# US29080671_sheet1.net
KiCad netlist of a schematic drawn in Altium Designer
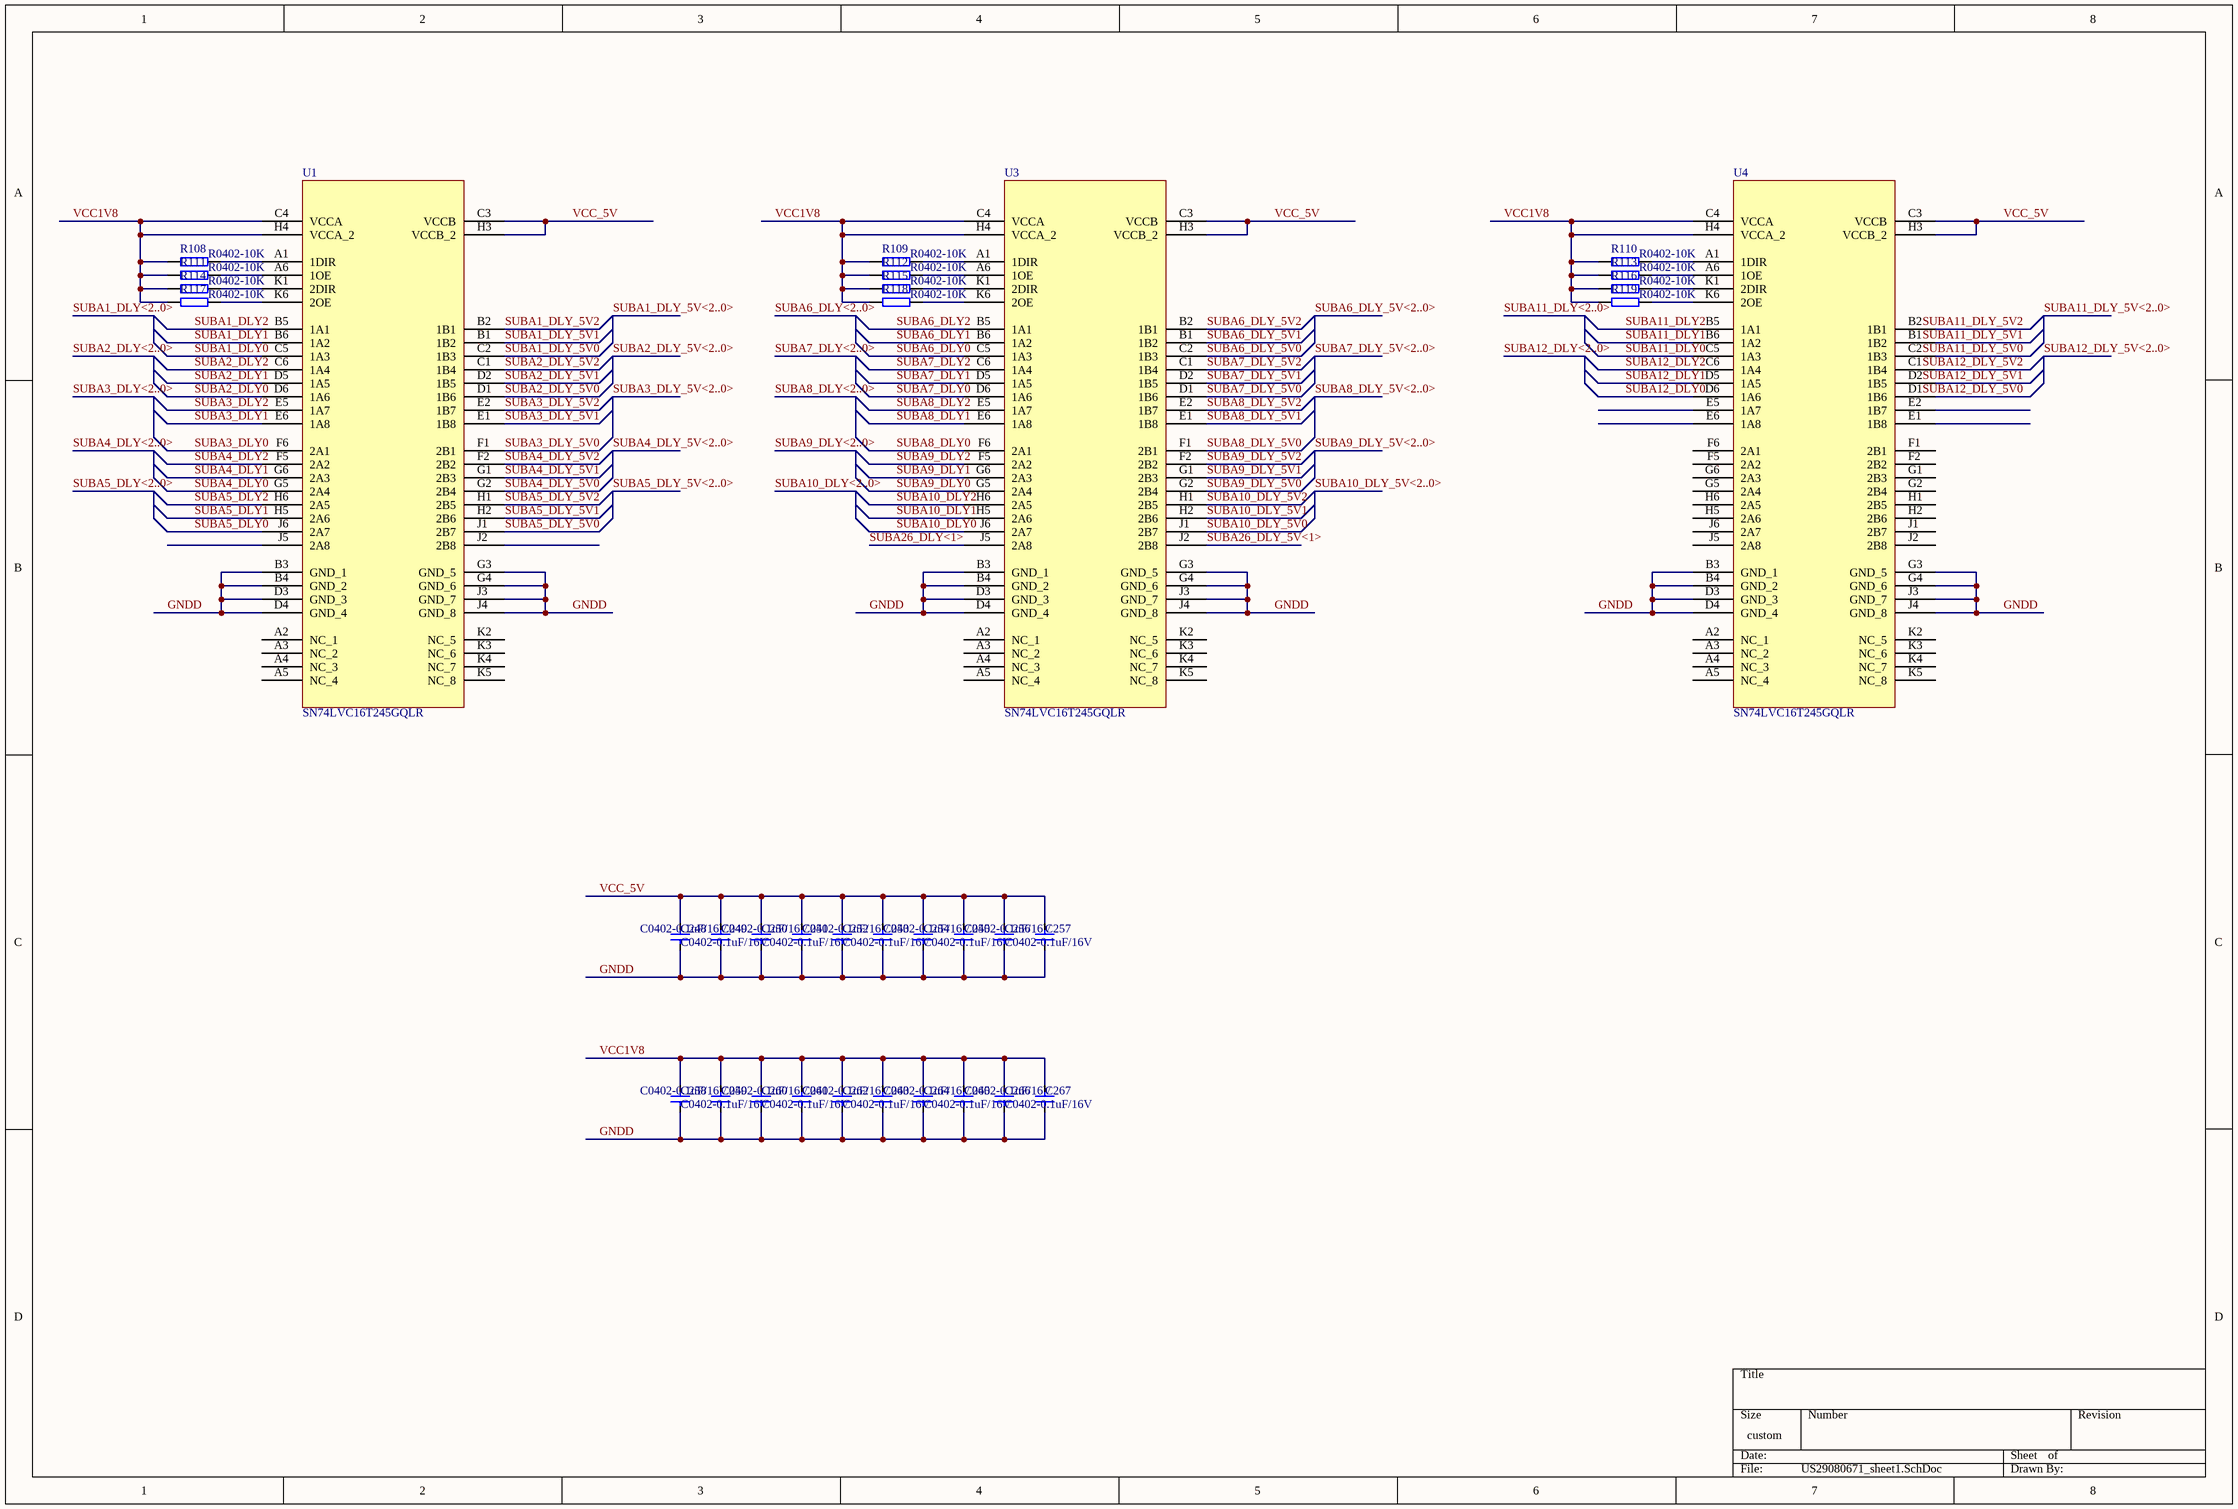
[diagram p0: US29080671_sheet1.SchDoc]

(export (version "E")
  (design (tool "Eeschema 10.0.6"))
  (components
    (comp (ref "C248")
      (value "C0402-0.1uF/16V")
      (footprint "C0402")
      (description "X7R")
      (fields (field (name "SCHEMATIC_PART") "CAP") (field (name "MANUFACTURER") "SAMSUNG"))
      (libsource (lib "Database_Libs1") (part "CAP"))
    )
    (comp (ref "C249")
      (value "C0402-0.1uF/16V")
      (footprint "C0402")
      (description "X7R")
      (fields (field (name "SCHEMATIC_PART") "CAP") (field (name "MANUFACTURER") "SAMSUNG"))
      (libsource (lib "Database_Libs1") (part "CAP"))
    )
    (comp (ref "C250")
      (value "C0402-0.1uF/16V")
      (footprint "C0402")
      (description "X7R")
      (fields (field (name "SCHEMATIC_PART") "CAP") (field (name "MANUFACTURER") "SAMSUNG"))
      (libsource (lib "Database_Libs1") (part "CAP"))
    )
    (comp (ref "C251")
      (value "C0402-0.1uF/16V")
      (footprint "C0402")
      (description "X7R")
      (fields (field (name "SCHEMATIC_PART") "CAP") (field (name "MANUFACTURER") "SAMSUNG"))
      (libsource (lib "Database_Libs1") (part "CAP"))
    )
    (comp (ref "C252")
      (value "C0402-0.1uF/16V")
      (footprint "C0402")
      (description "X7R")
      (fields (field (name "SCHEMATIC_PART") "CAP") (field (name "MANUFACTURER") "SAMSUNG"))
      (libsource (lib "Database_Libs1") (part "CAP"))
    )
    (comp (ref "C253")
      (value "C0402-0.1uF/16V")
      (footprint "C0402")
      (description "X7R")
      (fields (field (name "SCHEMATIC_PART") "CAP") (field (name "MANUFACTURER") "SAMSUNG"))
      (libsource (lib "Database_Libs1") (part "CAP"))
    )
    (comp (ref "C254")
      (value "C0402-0.1uF/16V")
      (footprint "C0402")
      (description "X7R")
      (fields (field (name "SCHEMATIC_PART") "CAP") (field (name "MANUFACTURER") "SAMSUNG"))
      (libsource (lib "Database_Libs1") (part "CAP"))
    )
    (comp (ref "C255")
      (value "C0402-0.1uF/16V")
      (footprint "C0402")
      (description "X7R")
      (fields (field (name "SCHEMATIC_PART") "CAP") (field (name "MANUFACTURER") "SAMSUNG"))
      (libsource (lib "Database_Libs1") (part "CAP"))
    )
    (comp (ref "C256")
      (value "C0402-0.1uF/16V")
      (footprint "C0402")
      (description "X7R")
      (fields (field (name "SCHEMATIC_PART") "CAP") (field (name "MANUFACTURER") "SAMSUNG"))
      (libsource (lib "Database_Libs1") (part "CAP"))
    )
    (comp (ref "C257")
      (value "C0402-0.1uF/16V")
      (footprint "C0402")
      (description "X7R")
      (fields (field (name "SCHEMATIC_PART") "CAP") (field (name "MANUFACTURER") "SAMSUNG"))
      (libsource (lib "Database_Libs1") (part "CAP"))
    )
    (comp (ref "C258")
      (value "C0402-0.1uF/16V")
      (footprint "C0402")
      (description "X7R")
      (fields (field (name "SCHEMATIC_PART") "CAP") (field (name "MANUFACTURER") "SAMSUNG"))
      (libsource (lib "Database_Libs1") (part "CAP"))
    )
    (comp (ref "C259")
      (value "C0402-0.1uF/16V")
      (footprint "C0402")
      (description "X7R")
      (fields (field (name "SCHEMATIC_PART") "CAP") (field (name "MANUFACTURER") "SAMSUNG"))
      (libsource (lib "Database_Libs1") (part "CAP"))
    )
    (comp (ref "C260")
      (value "C0402-0.1uF/16V")
      (footprint "C0402")
      (description "X7R")
      (fields (field (name "SCHEMATIC_PART") "CAP") (field (name "MANUFACTURER") "SAMSUNG"))
      (libsource (lib "Database_Libs1") (part "CAP"))
    )
    (comp (ref "C261")
      (value "C0402-0.1uF/16V")
      (footprint "C0402")
      (description "X7R")
      (fields (field (name "SCHEMATIC_PART") "CAP") (field (name "MANUFACTURER") "SAMSUNG"))
      (libsource (lib "Database_Libs1") (part "CAP"))
    )
    (comp (ref "C262")
      (value "C0402-0.1uF/16V")
      (footprint "C0402")
      (description "X7R")
      (fields (field (name "SCHEMATIC_PART") "CAP") (field (name "MANUFACTURER") "SAMSUNG"))
      (libsource (lib "Database_Libs1") (part "CAP"))
    )
    (comp (ref "C263")
      (value "C0402-0.1uF/16V")
      (footprint "C0402")
      (description "X7R")
      (fields (field (name "SCHEMATIC_PART") "CAP") (field (name "MANUFACTURER") "SAMSUNG"))
      (libsource (lib "Database_Libs1") (part "CAP"))
    )
    (comp (ref "C264")
      (value "C0402-0.1uF/16V")
      (footprint "C0402")
      (description "X7R")
      (fields (field (name "SCHEMATIC_PART") "CAP") (field (name "MANUFACTURER") "SAMSUNG"))
      (libsource (lib "Database_Libs1") (part "CAP"))
    )
    (comp (ref "C265")
      (value "C0402-0.1uF/16V")
      (footprint "C0402")
      (description "X7R")
      (fields (field (name "SCHEMATIC_PART") "CAP") (field (name "MANUFACTURER") "SAMSUNG"))
      (libsource (lib "Database_Libs1") (part "CAP"))
    )
    (comp (ref "C266")
      (value "C0402-0.1uF/16V")
      (footprint "C0402")
      (description "X7R")
      (fields (field (name "SCHEMATIC_PART") "CAP") (field (name "MANUFACTURER") "SAMSUNG"))
      (libsource (lib "Database_Libs1") (part "CAP"))
    )
    (comp (ref "C267")
      (value "C0402-0.1uF/16V")
      (footprint "C0402")
      (description "X7R")
      (fields (field (name "SCHEMATIC_PART") "CAP") (field (name "MANUFACTURER") "SAMSUNG"))
      (libsource (lib "Database_Libs1") (part "CAP"))
    )
    (comp (ref "R108")
      (value "R0402-10K")
      (footprint "R0402")
      (fields (field (name "SCHEMATIC_PART") "RES") (field (name "MANUFACTURER") "SAMSUNG"))
      (libsource (lib "Database_Libs1") (part "RES"))
    )
    (comp (ref "R109")
      (value "R0402-10K")
      (footprint "R0402")
      (fields (field (name "SCHEMATIC_PART") "RES") (field (name "MANUFACTURER") "SAMSUNG"))
      (libsource (lib "Database_Libs1") (part "RES"))
    )
    (comp (ref "R110")
      (value "R0402-10K")
      (footprint "R0402")
      (fields (field (name "SCHEMATIC_PART") "RES") (field (name "MANUFACTURER") "SAMSUNG"))
      (libsource (lib "Database_Libs1") (part "RES"))
    )
    (comp (ref "R111")
      (value "R0402-10K")
      (footprint "R0402")
      (fields (field (name "SCHEMATIC_PART") "RES") (field (name "MANUFACTURER") "SAMSUNG"))
      (libsource (lib "Database_Libs1") (part "RES"))
    )
    (comp (ref "R112")
      (value "R0402-10K")
      (footprint "R0402")
      (fields (field (name "SCHEMATIC_PART") "RES") (field (name "MANUFACTURER") "SAMSUNG"))
      (libsource (lib "Database_Libs1") (part "RES"))
    )
    (comp (ref "R113")
      (value "R0402-10K")
      (footprint "R0402")
      (fields (field (name "SCHEMATIC_PART") "RES") (field (name "MANUFACTURER") "SAMSUNG"))
      (libsource (lib "Database_Libs1") (part "RES"))
    )
    (comp (ref "R114")
      (value "R0402-10K")
      (footprint "R0402")
      (fields (field (name "SCHEMATIC_PART") "RES") (field (name "MANUFACTURER") "SAMSUNG"))
      (libsource (lib "Database_Libs1") (part "RES"))
    )
    (comp (ref "R115")
      (value "R0402-10K")
      (footprint "R0402")
      (fields (field (name "SCHEMATIC_PART") "RES") (field (name "MANUFACTURER") "SAMSUNG"))
      (libsource (lib "Database_Libs1") (part "RES"))
    )
    (comp (ref "R116")
      (value "R0402-10K")
      (footprint "R0402")
      (fields (field (name "SCHEMATIC_PART") "RES") (field (name "MANUFACTURER") "SAMSUNG"))
      (libsource (lib "Database_Libs1") (part "RES"))
    )
    (comp (ref "R117")
      (value "R0402-10K")
      (footprint "R0402")
      (fields (field (name "SCHEMATIC_PART") "RES") (field (name "MANUFACTURER") "SAMSUNG"))
      (libsource (lib "Database_Libs1") (part "RES"))
    )
    (comp (ref "R118")
      (value "R0402-10K")
      (footprint "R0402")
      (fields (field (name "SCHEMATIC_PART") "RES") (field (name "MANUFACTURER") "SAMSUNG"))
      (libsource (lib "Database_Libs1") (part "RES"))
    )
    (comp (ref "R119")
      (value "R0402-10K")
      (footprint "R0402")
      (fields (field (name "SCHEMATIC_PART") "RES") (field (name "MANUFACTURER") "SAMSUNG"))
      (libsource (lib "Database_Libs1") (part "RES"))
    )
    (comp (ref "U1")
      (value "SN74LVC16T245GQLR")
      (footprint "BGA-56")
      (libsource (lib "SCHLIB1") (part "SN74LVC16T245"))
    )
    (comp (ref "U3")
      (value "SN74LVC16T245GQLR")
      (footprint "BGA-56")
      (libsource (lib "SCHLIB1") (part "SN74LVC16T245"))
    )
    (comp (ref "U4")
      (value "SN74LVC16T245GQLR")
      (footprint "BGA-56")
      (libsource (lib "SCHLIB1") (part "SN74LVC16T245"))
    )
  )
  (nets
    (net (code "25") (name "/GNDD") (class "Default")
      (node (ref "C248") (pin "2") (pinfunction "2_2") (pintype "passive"))
      (node (ref "C249") (pin "2") (pinfunction "2_2") (pintype "passive"))
      (node (ref "C250") (pin "2") (pinfunction "2_2") (pintype "passive"))
      (node (ref "C251") (pin "2") (pinfunction "2_2") (pintype "passive"))
      (node (ref "C252") (pin "2") (pinfunction "2_2") (pintype "passive"))
      (node (ref "C253") (pin "2") (pinfunction "2_2") (pintype "passive"))
      (node (ref "C254") (pin "2") (pinfunction "2_2") (pintype "passive"))
      (node (ref "C255") (pin "2") (pinfunction "2_2") (pintype "passive"))
      (node (ref "C256") (pin "2") (pinfunction "2_2") (pintype "passive"))
      (node (ref "C257") (pin "2") (pinfunction "2_2") (pintype "passive"))
      (node (ref "C258") (pin "2") (pinfunction "2_2") (pintype "passive"))
      (node (ref "C259") (pin "2") (pinfunction "2_2") (pintype "passive"))
      (node (ref "C260") (pin "2") (pinfunction "2_2") (pintype "passive"))
      (node (ref "C261") (pin "2") (pinfunction "2_2") (pintype "passive"))
      (node (ref "C262") (pin "2") (pinfunction "2_2") (pintype "passive"))
      (node (ref "C263") (pin "2") (pinfunction "2_2") (pintype "passive"))
      (node (ref "C264") (pin "2") (pinfunction "2_2") (pintype "passive"))
      (node (ref "C265") (pin "2") (pinfunction "2_2") (pintype "passive"))
      (node (ref "C266") (pin "2") (pinfunction "2_2") (pintype "passive"))
      (node (ref "C267") (pin "2") (pinfunction "2_2") (pintype "passive"))
      (node (ref "U1") (pin "B3") (pinfunction "GND_1_B3") (pintype "passive"))
      (node (ref "U1") (pin "B4") (pinfunction "GND_2_B4") (pintype "passive"))
      (node (ref "U1") (pin "D3") (pinfunction "GND_3_D3") (pintype "passive"))
      (node (ref "U1") (pin "D4") (pinfunction "GND_4_D4") (pintype "passive"))
      (node (ref "U1") (pin "G3") (pinfunction "GND_5_G3") (pintype "passive"))
      (node (ref "U1") (pin "G4") (pinfunction "GND_6_G4") (pintype "passive"))
      (node (ref "U1") (pin "J3") (pinfunction "GND_7_J3") (pintype "passive"))
      (node (ref "U1") (pin "J4") (pinfunction "GND_8_J4") (pintype "passive"))
      (node (ref "U3") (pin "B3") (pinfunction "GND_1_B3") (pintype "passive"))
      (node (ref "U3") (pin "B4") (pinfunction "GND_2_B4") (pintype "passive"))
      (node (ref "U3") (pin "D3") (pinfunction "GND_3_D3") (pintype "passive"))
      (node (ref "U3") (pin "D4") (pinfunction "GND_4_D4") (pintype "passive"))
      (node (ref "U3") (pin "G3") (pinfunction "GND_5_G3") (pintype "passive"))
      (node (ref "U3") (pin "G4") (pinfunction "GND_6_G4") (pintype "passive"))
      (node (ref "U3") (pin "J3") (pinfunction "GND_7_J3") (pintype "passive"))
      (node (ref "U3") (pin "J4") (pinfunction "GND_8_J4") (pintype "passive"))
      (node (ref "U4") (pin "B3") (pinfunction "GND_1_B3") (pintype "passive"))
      (node (ref "U4") (pin "B4") (pinfunction "GND_2_B4") (pintype "passive"))
      (node (ref "U4") (pin "D3") (pinfunction "GND_3_D3") (pintype "passive"))
      (node (ref "U4") (pin "D4") (pinfunction "GND_4_D4") (pintype "passive"))
      (node (ref "U4") (pin "G3") (pinfunction "GND_5_G3") (pintype "passive"))
      (node (ref "U4") (pin "G4") (pinfunction "GND_6_G4") (pintype "passive"))
      (node (ref "U4") (pin "J3") (pinfunction "GND_7_J3") (pintype "passive"))
      (node (ref "U4") (pin "J4") (pinfunction "GND_8_J4") (pintype "passive"))
    )
    (net (code "26") (name "/SUBA1_DLY0") (class "Default")
      (node (ref "U1") (pin "C5") (pinfunction "1A3_C5") (pintype "passive"))
    )
    (net (code "27") (name "/SUBA1_DLY1") (class "Default")
      (node (ref "U1") (pin "B6") (pinfunction "1A2_B6") (pintype "passive"))
    )
    (net (code "28") (name "/SUBA1_DLY2") (class "Default")
      (node (ref "U1") (pin "B5") (pinfunction "1A1_B5") (pintype "passive"))
    )
    (net (code "29") (name "/SUBA1_DLY_5V0") (class "Default")
      (node (ref "U1") (pin "C2") (pinfunction "1B3_C2") (pintype "passive"))
    )
    (net (code "30") (name "/SUBA1_DLY_5V1") (class "Default")
      (node (ref "U1") (pin "B1") (pinfunction "1B2_B1") (pintype "passive"))
    )
    (net (code "31") (name "/SUBA1_DLY_5V2") (class "Default")
      (node (ref "U1") (pin "B2") (pinfunction "1B1_B2") (pintype "passive"))
    )
    (net (code "32") (name "/SUBA2_DLY0") (class "Default")
      (node (ref "U1") (pin "D6") (pinfunction "1A6_D6") (pintype "passive"))
    )
    (net (code "33") (name "/SUBA2_DLY1") (class "Default")
      (node (ref "U1") (pin "D5") (pinfunction "1A5_D5") (pintype "passive"))
    )
    (net (code "34") (name "/SUBA2_DLY2") (class "Default")
      (node (ref "U1") (pin "C6") (pinfunction "1A4_C6") (pintype "passive"))
    )
    (net (code "35") (name "/SUBA2_DLY_5V0") (class "Default")
      (node (ref "U1") (pin "D1") (pinfunction "1B6_D1") (pintype "passive"))
    )
    (net (code "36") (name "/SUBA2_DLY_5V1") (class "Default")
      (node (ref "U1") (pin "D2") (pinfunction "1B5_D2") (pintype "passive"))
    )
    (net (code "37") (name "/SUBA2_DLY_5V2") (class "Default")
      (node (ref "U1") (pin "C1") (pinfunction "1B4_C1") (pintype "passive"))
    )
    (net (code "38") (name "/SUBA3_DLY0") (class "Default")
      (node (ref "U1") (pin "F6") (pinfunction "2A1_F6") (pintype "passive"))
    )
    (net (code "39") (name "/SUBA3_DLY1") (class "Default")
      (node (ref "U1") (pin "E6") (pinfunction "1A8_E6") (pintype "passive"))
    )
    (net (code "40") (name "/SUBA3_DLY2") (class "Default")
      (node (ref "U1") (pin "E5") (pinfunction "1A7_E5") (pintype "passive"))
    )
    (net (code "41") (name "/SUBA3_DLY_5V0") (class "Default")
      (node (ref "U1") (pin "F1") (pinfunction "2B1_F1") (pintype "passive"))
    )
    (net (code "42") (name "/SUBA3_DLY_5V1") (class "Default")
      (node (ref "U1") (pin "E1") (pinfunction "1B8_E1") (pintype "passive"))
    )
    (net (code "43") (name "/SUBA3_DLY_5V2") (class "Default")
      (node (ref "U1") (pin "E2") (pinfunction "1B7_E2") (pintype "passive"))
    )
    (net (code "44") (name "/SUBA4_DLY0") (class "Default")
      (node (ref "U1") (pin "G5") (pinfunction "2A4_G5") (pintype "passive"))
    )
    (net (code "45") (name "/SUBA4_DLY1") (class "Default")
      (node (ref "U1") (pin "G6") (pinfunction "2A3_G6") (pintype "passive"))
    )
    (net (code "46") (name "/SUBA4_DLY2") (class "Default")
      (node (ref "U1") (pin "F5") (pinfunction "2A2_F5") (pintype "passive"))
    )
    (net (code "47") (name "/SUBA4_DLY_5V0") (class "Default")
      (node (ref "U1") (pin "G2") (pinfunction "2B4_G2") (pintype "passive"))
    )
    (net (code "48") (name "/SUBA4_DLY_5V1") (class "Default")
      (node (ref "U1") (pin "G1") (pinfunction "2B3_G1") (pintype "passive"))
    )
    (net (code "49") (name "/SUBA4_DLY_5V2") (class "Default")
      (node (ref "U1") (pin "F2") (pinfunction "2B2_F2") (pintype "passive"))
    )
    (net (code "50") (name "/SUBA5_DLY0") (class "Default")
      (node (ref "U1") (pin "J6") (pinfunction "2A7_J6") (pintype "passive"))
    )
    (net (code "51") (name "/SUBA5_DLY1") (class "Default")
      (node (ref "U1") (pin "H5") (pinfunction "2A6_H5") (pintype "passive"))
    )
    (net (code "52") (name "/SUBA5_DLY2") (class "Default")
      (node (ref "U1") (pin "H6") (pinfunction "2A5_H6") (pintype "passive"))
    )
    (net (code "53") (name "/SUBA5_DLY_5V0") (class "Default")
      (node (ref "U1") (pin "J1") (pinfunction "2B7_J1") (pintype "passive"))
    )
    (net (code "54") (name "/SUBA5_DLY_5V1") (class "Default")
      (node (ref "U1") (pin "H2") (pinfunction "2B6_H2") (pintype "passive"))
    )
    (net (code "55") (name "/SUBA5_DLY_5V2") (class "Default")
      (node (ref "U1") (pin "H1") (pinfunction "2B5_H1") (pintype "passive"))
    )
    (net (code "56") (name "/SUBA6_DLY0") (class "Default")
      (node (ref "U3") (pin "C5") (pinfunction "1A3_C5") (pintype "passive"))
    )
    (net (code "57") (name "/SUBA6_DLY1") (class "Default")
      (node (ref "U3") (pin "B6") (pinfunction "1A2_B6") (pintype "passive"))
    )
    (net (code "58") (name "/SUBA6_DLY2") (class "Default")
      (node (ref "U3") (pin "B5") (pinfunction "1A1_B5") (pintype "passive"))
    )
    (net (code "59") (name "/SUBA6_DLY_5V0") (class "Default")
      (node (ref "U3") (pin "C2") (pinfunction "1B3_C2") (pintype "passive"))
    )
    (net (code "60") (name "/SUBA6_DLY_5V1") (class "Default")
      (node (ref "U3") (pin "B1") (pinfunction "1B2_B1") (pintype "passive"))
    )
    (net (code "61") (name "/SUBA6_DLY_5V2") (class "Default")
      (node (ref "U3") (pin "B2") (pinfunction "1B1_B2") (pintype "passive"))
    )
    (net (code "62") (name "/SUBA7_DLY0") (class "Default")
      (node (ref "U3") (pin "D6") (pinfunction "1A6_D6") (pintype "passive"))
    )
    (net (code "63") (name "/SUBA7_DLY1") (class "Default")
      (node (ref "U3") (pin "D5") (pinfunction "1A5_D5") (pintype "passive"))
    )
    (net (code "64") (name "/SUBA7_DLY2") (class "Default")
      (node (ref "U3") (pin "C6") (pinfunction "1A4_C6") (pintype "passive"))
    )
    (net (code "65") (name "/SUBA7_DLY_5V0") (class "Default")
      (node (ref "U3") (pin "D1") (pinfunction "1B6_D1") (pintype "passive"))
    )
    (net (code "66") (name "/SUBA7_DLY_5V1") (class "Default")
      (node (ref "U3") (pin "D2") (pinfunction "1B5_D2") (pintype "passive"))
    )
    (net (code "67") (name "/SUBA7_DLY_5V2") (class "Default")
      (node (ref "U3") (pin "C1") (pinfunction "1B4_C1") (pintype "passive"))
    )
    (net (code "68") (name "/SUBA8_DLY0") (class "Default")
      (node (ref "U3") (pin "F6") (pinfunction "2A1_F6") (pintype "passive"))
    )
    (net (code "69") (name "/SUBA8_DLY1") (class "Default")
      (node (ref "U3") (pin "E6") (pinfunction "1A8_E6") (pintype "passive"))
    )
    (net (code "70") (name "/SUBA8_DLY2") (class "Default")
      (node (ref "U3") (pin "E5") (pinfunction "1A7_E5") (pintype "passive"))
    )
    (net (code "71") (name "/SUBA8_DLY_5V0") (class "Default")
      (node (ref "U3") (pin "F1") (pinfunction "2B1_F1") (pintype "passive"))
    )
    (net (code "72") (name "/SUBA8_DLY_5V1") (class "Default")
      (node (ref "U3") (pin "E1") (pinfunction "1B8_E1") (pintype "passive"))
    )
    (net (code "73") (name "/SUBA8_DLY_5V2") (class "Default")
      (node (ref "U3") (pin "E2") (pinfunction "1B7_E2") (pintype "passive"))
    )
    (net (code "74") (name "/SUBA9_DLY0") (class "Default")
      (node (ref "U3") (pin "G5") (pinfunction "2A4_G5") (pintype "passive"))
    )
    (net (code "75") (name "/SUBA9_DLY1") (class "Default")
      (node (ref "U3") (pin "G6") (pinfunction "2A3_G6") (pintype "passive"))
    )
    (net (code "76") (name "/SUBA9_DLY2") (class "Default")
      (node (ref "U3") (pin "F5") (pinfunction "2A2_F5") (pintype "passive"))
    )
    (net (code "77") (name "/SUBA9_DLY_5V0") (class "Default")
      (node (ref "U3") (pin "G2") (pinfunction "2B4_G2") (pintype "passive"))
    )
    (net (code "78") (name "/SUBA9_DLY_5V1") (class "Default")
      (node (ref "U3") (pin "G1") (pinfunction "2B3_G1") (pintype "passive"))
    )
    (net (code "79") (name "/SUBA9_DLY_5V2") (class "Default")
      (node (ref "U3") (pin "F2") (pinfunction "2B2_F2") (pintype "passive"))
    )
    (net (code "80") (name "/SUBA10_DLY0") (class "Default")
      (node (ref "U3") (pin "J6") (pinfunction "2A7_J6") (pintype "passive"))
    )
    (net (code "81") (name "/SUBA10_DLY1") (class "Default")
      (node (ref "U3") (pin "H5") (pinfunction "2A6_H5") (pintype "passive"))
    )
    (net (code "82") (name "/SUBA10_DLY2") (class "Default")
      (node (ref "U3") (pin "H6") (pinfunction "2A5_H6") (pintype "passive"))
    )
    (net (code "83") (name "/SUBA10_DLY_5V0") (class "Default")
      (node (ref "U3") (pin "J1") (pinfunction "2B7_J1") (pintype "passive"))
    )
    (net (code "84") (name "/SUBA10_DLY_5V1") (class "Default")
      (node (ref "U3") (pin "H2") (pinfunction "2B6_H2") (pintype "passive"))
    )
    (net (code "85") (name "/SUBA10_DLY_5V2") (class "Default")
      (node (ref "U3") (pin "H1") (pinfunction "2B5_H1") (pintype "passive"))
    )
    (net (code "86") (name "/SUBA11_DLY0") (class "Default")
      (node (ref "U4") (pin "C5") (pinfunction "1A3_C5") (pintype "passive"))
    )
    (net (code "87") (name "/SUBA11_DLY1") (class "Default")
      (node (ref "U4") (pin "B6") (pinfunction "1A2_B6") (pintype "passive"))
    )
    (net (code "88") (name "/SUBA11_DLY2") (class "Default")
      (node (ref "U4") (pin "B5") (pinfunction "1A1_B5") (pintype "passive"))
    )
    (net (code "92") (name "/SUBA12_DLY0") (class "Default")
      (node (ref "U4") (pin "D6") (pinfunction "1A6_D6") (pintype "passive"))
    )
    (net (code "93") (name "/SUBA12_DLY1") (class "Default")
      (node (ref "U4") (pin "D5") (pinfunction "1A5_D5") (pintype "passive"))
    )
    (net (code "94") (name "/SUBA12_DLY2") (class "Default")
      (node (ref "U4") (pin "C6") (pinfunction "1A4_C6") (pintype "passive"))
    )
    (net (code "98") (name "/SUBA26_DLY<1>") (class "Default")
      (node (ref "U3") (pin "J5") (pinfunction "2A8_J5") (pintype "passive"))
    )
    (net (code "99") (name "/SUBA26_DLY_5V<1>") (class "Default")
      (node (ref "U3") (pin "J2") (pinfunction "2B8_J2") (pintype "passive"))
    )
    (net (code "100") (name "/VCC1V8") (class "Default")
      (node (ref "C258") (pin "1") (pinfunction "1_1") (pintype "passive"))
      (node (ref "C259") (pin "1") (pinfunction "1_1") (pintype "passive"))
      (node (ref "C260") (pin "1") (pinfunction "1_1") (pintype "passive"))
      (node (ref "C261") (pin "1") (pinfunction "1_1") (pintype "passive"))
      (node (ref "C262") (pin "1") (pinfunction "1_1") (pintype "passive"))
      (node (ref "C263") (pin "1") (pinfunction "1_1") (pintype "passive"))
      (node (ref "C264") (pin "1") (pinfunction "1_1") (pintype "passive"))
      (node (ref "C265") (pin "1") (pinfunction "1_1") (pintype "passive"))
      (node (ref "C266") (pin "1") (pinfunction "1_1") (pintype "passive"))
      (node (ref "C267") (pin "1") (pinfunction "1_1") (pintype "passive"))
      (node (ref "R108") (pin "1") (pintype "passive"))
      (node (ref "R109") (pin "1") (pintype "passive"))
      (node (ref "R110") (pin "1") (pintype "passive"))
      (node (ref "R111") (pin "1") (pintype "passive"))
      (node (ref "R112") (pin "1") (pintype "passive"))
      (node (ref "R113") (pin "1") (pintype "passive"))
      (node (ref "R114") (pin "1") (pintype "passive"))
      (node (ref "R115") (pin "1") (pintype "passive"))
      (node (ref "R116") (pin "1") (pintype "passive"))
      (node (ref "R117") (pin "1") (pintype "passive"))
      (node (ref "R118") (pin "1") (pintype "passive"))
      (node (ref "R119") (pin "1") (pintype "passive"))
      (node (ref "U1") (pin "C4") (pinfunction "VCCA_C4") (pintype "passive"))
      (node (ref "U1") (pin "H4") (pinfunction "VCCA_2_H4") (pintype "passive"))
      (node (ref "U3") (pin "C4") (pinfunction "VCCA_C4") (pintype "passive"))
      (node (ref "U3") (pin "H4") (pinfunction "VCCA_2_H4") (pintype "passive"))
      (node (ref "U4") (pin "C4") (pinfunction "VCCA_C4") (pintype "passive"))
      (node (ref "U4") (pin "H4") (pinfunction "VCCA_2_H4") (pintype "passive"))
    )
    (net (code "101") (name "/VCC_5V") (class "Default")
      (node (ref "C248") (pin "1") (pinfunction "1_1") (pintype "passive"))
      (node (ref "C249") (pin "1") (pinfunction "1_1") (pintype "passive"))
      (node (ref "C250") (pin "1") (pinfunction "1_1") (pintype "passive"))
      (node (ref "C251") (pin "1") (pinfunction "1_1") (pintype "passive"))
      (node (ref "C252") (pin "1") (pinfunction "1_1") (pintype "passive"))
      (node (ref "C253") (pin "1") (pinfunction "1_1") (pintype "passive"))
      (node (ref "C254") (pin "1") (pinfunction "1_1") (pintype "passive"))
      (node (ref "C255") (pin "1") (pinfunction "1_1") (pintype "passive"))
      (node (ref "C256") (pin "1") (pinfunction "1_1") (pintype "passive"))
      (node (ref "C257") (pin "1") (pinfunction "1_1") (pintype "passive"))
      (node (ref "U1") (pin "C3") (pinfunction "VCCB_C3") (pintype "passive"))
      (node (ref "U1") (pin "H3") (pinfunction "VCCB_2_H3") (pintype "passive"))
      (node (ref "U3") (pin "C3") (pinfunction "VCCB_C3") (pintype "passive"))
      (node (ref "U3") (pin "H3") (pinfunction "VCCB_2_H3") (pintype "passive"))
      (node (ref "U4") (pin "C3") (pinfunction "VCCB_C3") (pintype "passive"))
      (node (ref "U4") (pin "H3") (pinfunction "VCCB_2_H3") (pintype "passive"))
    )
    (net (code "126") (name "Net-(U1-1DIR)") (class "Default")
      (node (ref "R108") (pin "2") (pintype "passive"))
      (node (ref "U1") (pin "A1") (pinfunction "1DIR_A1") (pintype "passive"))
    )
    (net (code "127") (name "Net-(U1-1OE)") (class "Default")
      (node (ref "R111") (pin "2") (pintype "passive"))
      (node (ref "U1") (pin "A6") (pinfunction "1OE_A6") (pintype "passive"))
    )
    (net (code "128") (name "Net-(U1-2DIR)") (class "Default")
      (node (ref "R114") (pin "2") (pintype "passive"))
      (node (ref "U1") (pin "K1") (pinfunction "2DIR_K1") (pintype "passive"))
    )
    (net (code "129") (name "Net-(U1-2OE)") (class "Default")
      (node (ref "R117") (pin "2") (pintype "passive"))
      (node (ref "U1") (pin "K6") (pinfunction "2OE_K6") (pintype "passive"))
    )
    (net (code "130") (name "Net-(U3-1DIR)") (class "Default")
      (node (ref "R109") (pin "2") (pintype "passive"))
      (node (ref "U3") (pin "A1") (pinfunction "1DIR_A1") (pintype "passive"))
    )
    (net (code "131") (name "Net-(U3-1OE)") (class "Default")
      (node (ref "R112") (pin "2") (pintype "passive"))
      (node (ref "U3") (pin "A6") (pinfunction "1OE_A6") (pintype "passive"))
    )
    (net (code "132") (name "Net-(U3-2DIR)") (class "Default")
      (node (ref "R115") (pin "2") (pintype "passive"))
      (node (ref "U3") (pin "K1") (pinfunction "2DIR_K1") (pintype "passive"))
    )
    (net (code "133") (name "Net-(U3-2OE)") (class "Default")
      (node (ref "R118") (pin "2") (pintype "passive"))
      (node (ref "U3") (pin "K6") (pinfunction "2OE_K6") (pintype "passive"))
    )
    (net (code "134") (name "Net-(U4-1DIR)") (class "Default")
      (node (ref "R110") (pin "2") (pintype "passive"))
      (node (ref "U4") (pin "A1") (pinfunction "1DIR_A1") (pintype "passive"))
    )
    (net (code "135") (name "Net-(U4-1OE)") (class "Default")
      (node (ref "R113") (pin "2") (pintype "passive"))
      (node (ref "U4") (pin "A6") (pinfunction "1OE_A6") (pintype "passive"))
    )
    (net (code "136") (name "Net-(U4-2DIR)") (class "Default")
      (node (ref "R116") (pin "2") (pintype "passive"))
      (node (ref "U4") (pin "K1") (pinfunction "2DIR_K1") (pintype "passive"))
    )
    (net (code "137") (name "Net-(U4-2OE)") (class "Default")
      (node (ref "R119") (pin "2") (pintype "passive"))
      (node (ref "U4") (pin "K6") (pinfunction "2OE_K6") (pintype "passive"))
    )
    (net (code "138") (name "unconnected-(U1-2A8-PadJ5)") (class "Default")
      (node (ref "U1") (pin "J5") (pinfunction "2A8_J5") (pintype "passive"))
    )
    (net (code "139") (name "unconnected-(U1-2B8-PadJ2)") (class "Default")
      (node (ref "U1") (pin "J2") (pinfunction "2B8_J2") (pintype "passive"))
    )
    (net (code "140") (name "unconnected-(U1-NC_1-PadA2)") (class "Default")
      (node (ref "U1") (pin "A2") (pinfunction "NC_1_A2") (pintype "passive"))
    )
    (net (code "141") (name "unconnected-(U1-NC_2-PadA3)") (class "Default")
      (node (ref "U1") (pin "A3") (pinfunction "NC_2_A3") (pintype "passive"))
    )
    (net (code "142") (name "unconnected-(U1-NC_3-PadA4)") (class "Default")
      (node (ref "U1") (pin "A4") (pinfunction "NC_3_A4") (pintype "passive"))
    )
    (net (code "143") (name "unconnected-(U1-NC_4-PadA5)") (class "Default")
      (node (ref "U1") (pin "A5") (pinfunction "NC_4_A5") (pintype "passive"))
    )
    (net (code "144") (name "unconnected-(U1-NC_5-PadK2)") (class "Default")
      (node (ref "U1") (pin "K2") (pinfunction "NC_5_K2") (pintype "passive"))
    )
    (net (code "145") (name "unconnected-(U1-NC_6-PadK3)") (class "Default")
      (node (ref "U1") (pin "K3") (pinfunction "NC_6_K3") (pintype "passive"))
    )
    (net (code "146") (name "unconnected-(U1-NC_7-PadK4)") (class "Default")
      (node (ref "U1") (pin "K4") (pinfunction "NC_7_K4") (pintype "passive"))
    )
    (net (code "147") (name "unconnected-(U1-NC_8-PadK5)") (class "Default")
      (node (ref "U1") (pin "K5") (pinfunction "NC_8_K5") (pintype "passive"))
    )
    (net (code "148") (name "unconnected-(U3-NC_1-PadA2)") (class "Default")
      (node (ref "U3") (pin "A2") (pinfunction "NC_1_A2") (pintype "passive"))
    )
    (net (code "149") (name "unconnected-(U3-NC_2-PadA3)") (class "Default")
      (node (ref "U3") (pin "A3") (pinfunction "NC_2_A3") (pintype "passive"))
    )
    (net (code "150") (name "unconnected-(U3-NC_3-PadA4)") (class "Default")
      (node (ref "U3") (pin "A4") (pinfunction "NC_3_A4") (pintype "passive"))
    )
    (net (code "151") (name "unconnected-(U3-NC_4-PadA5)") (class "Default")
      (node (ref "U3") (pin "A5") (pinfunction "NC_4_A5") (pintype "passive"))
    )
    (net (code "152") (name "unconnected-(U3-NC_5-PadK2)") (class "Default")
      (node (ref "U3") (pin "K2") (pinfunction "NC_5_K2") (pintype "passive"))
    )
    (net (code "153") (name "unconnected-(U3-NC_6-PadK3)") (class "Default")
      (node (ref "U3") (pin "K3") (pinfunction "NC_6_K3") (pintype "passive"))
    )
    (net (code "154") (name "unconnected-(U3-NC_7-PadK4)") (class "Default")
      (node (ref "U3") (pin "K4") (pinfunction "NC_7_K4") (pintype "passive"))
    )
    (net (code "155") (name "unconnected-(U3-NC_8-PadK5)") (class "Default")
      (node (ref "U3") (pin "K5") (pinfunction "NC_8_K5") (pintype "passive"))
    )
    (net (code "156") (name "unconnected-(U4-1A7-PadE5)") (class "Default")
      (node (ref "U4") (pin "E5") (pinfunction "1A7_E5") (pintype "passive"))
    )
    (net (code "157") (name "unconnected-(U4-1A8-PadE6)") (class "Default")
      (node (ref "U4") (pin "E6") (pinfunction "1A8_E6") (pintype "passive"))
    )
    (net (code "158") (name "unconnected-(U4-1B1-PadB2)") (class "Default")
      (node (ref "U4") (pin "B2") (pinfunction "1B1_B2") (pintype "passive"))
    )
    (net (code "159") (name "unconnected-(U4-1B2-PadB1)") (class "Default")
      (node (ref "U4") (pin "B1") (pinfunction "1B2_B1") (pintype "passive"))
    )
    (net (code "160") (name "unconnected-(U4-1B3-PadC2)") (class "Default")
      (node (ref "U4") (pin "C2") (pinfunction "1B3_C2") (pintype "passive"))
    )
    (net (code "161") (name "unconnected-(U4-1B4-PadC1)") (class "Default")
      (node (ref "U4") (pin "C1") (pinfunction "1B4_C1") (pintype "passive"))
    )
    (net (code "162") (name "unconnected-(U4-1B5-PadD2)") (class "Default")
      (node (ref "U4") (pin "D2") (pinfunction "1B5_D2") (pintype "passive"))
    )
    (net (code "163") (name "unconnected-(U4-1B6-PadD1)") (class "Default")
      (node (ref "U4") (pin "D1") (pinfunction "1B6_D1") (pintype "passive"))
    )
    (net (code "164") (name "unconnected-(U4-1B7-PadE2)") (class "Default")
      (node (ref "U4") (pin "E2") (pinfunction "1B7_E2") (pintype "passive"))
    )
    (net (code "165") (name "unconnected-(U4-1B8-PadE1)") (class "Default")
      (node (ref "U4") (pin "E1") (pinfunction "1B8_E1") (pintype "passive"))
    )
    (net (code "166") (name "unconnected-(U4-2A1-PadF6)") (class "Default")
      (node (ref "U4") (pin "F6") (pinfunction "2A1_F6") (pintype "passive"))
    )
    (net (code "167") (name "unconnected-(U4-2A2-PadF5)") (class "Default")
      (node (ref "U4") (pin "F5") (pinfunction "2A2_F5") (pintype "passive"))
    )
    (net (code "168") (name "unconnected-(U4-2A3-PadG6)") (class "Default")
      (node (ref "U4") (pin "G6") (pinfunction "2A3_G6") (pintype "passive"))
    )
    (net (code "169") (name "unconnected-(U4-2A4-PadG5)") (class "Default")
      (node (ref "U4") (pin "G5") (pinfunction "2A4_G5") (pintype "passive"))
    )
    (net (code "170") (name "unconnected-(U4-2A5-PadH6)") (class "Default")
      (node (ref "U4") (pin "H6") (pinfunction "2A5_H6") (pintype "passive"))
    )
    (net (code "171") (name "unconnected-(U4-2A6-PadH5)") (class "Default")
      (node (ref "U4") (pin "H5") (pinfunction "2A6_H5") (pintype "passive"))
    )
    (net (code "172") (name "unconnected-(U4-2A7-PadJ6)") (class "Default")
      (node (ref "U4") (pin "J6") (pinfunction "2A7_J6") (pintype "passive"))
    )
    (net (code "173") (name "unconnected-(U4-2A8-PadJ5)") (class "Default")
      (node (ref "U4") (pin "J5") (pinfunction "2A8_J5") (pintype "passive"))
    )
    (net (code "174") (name "unconnected-(U4-2B1-PadF1)") (class "Default")
      (node (ref "U4") (pin "F1") (pinfunction "2B1_F1") (pintype "passive"))
    )
    (net (code "175") (name "unconnected-(U4-2B2-PadF2)") (class "Default")
      (node (ref "U4") (pin "F2") (pinfunction "2B2_F2") (pintype "passive"))
    )
    (net (code "176") (name "unconnected-(U4-2B3-PadG1)") (class "Default")
      (node (ref "U4") (pin "G1") (pinfunction "2B3_G1") (pintype "passive"))
    )
    (net (code "177") (name "unconnected-(U4-2B4-PadG2)") (class "Default")
      (node (ref "U4") (pin "G2") (pinfunction "2B4_G2") (pintype "passive"))
    )
    (net (code "178") (name "unconnected-(U4-2B5-PadH1)") (class "Default")
      (node (ref "U4") (pin "H1") (pinfunction "2B5_H1") (pintype "passive"))
    )
    (net (code "179") (name "unconnected-(U4-2B6-PadH2)") (class "Default")
      (node (ref "U4") (pin "H2") (pinfunction "2B6_H2") (pintype "passive"))
    )
    (net (code "180") (name "unconnected-(U4-2B7-PadJ1)") (class "Default")
      (node (ref "U4") (pin "J1") (pinfunction "2B7_J1") (pintype "passive"))
    )
    (net (code "181") (name "unconnected-(U4-2B8-PadJ2)") (class "Default")
      (node (ref "U4") (pin "J2") (pinfunction "2B8_J2") (pintype "passive"))
    )
    (net (code "182") (name "unconnected-(U4-NC_1-PadA2)") (class "Default")
      (node (ref "U4") (pin "A2") (pinfunction "NC_1_A2") (pintype "passive"))
    )
    (net (code "183") (name "unconnected-(U4-NC_2-PadA3)") (class "Default")
      (node (ref "U4") (pin "A3") (pinfunction "NC_2_A3") (pintype "passive"))
    )
    (net (code "184") (name "unconnected-(U4-NC_3-PadA4)") (class "Default")
      (node (ref "U4") (pin "A4") (pinfunction "NC_3_A4") (pintype "passive"))
    )
    (net (code "185") (name "unconnected-(U4-NC_4-PadA5)") (class "Default")
      (node (ref "U4") (pin "A5") (pinfunction "NC_4_A5") (pintype "passive"))
    )
    (net (code "186") (name "unconnected-(U4-NC_5-PadK2)") (class "Default")
      (node (ref "U4") (pin "K2") (pinfunction "NC_5_K2") (pintype "passive"))
    )
    (net (code "187") (name "unconnected-(U4-NC_6-PadK3)") (class "Default")
      (node (ref "U4") (pin "K3") (pinfunction "NC_6_K3") (pintype "passive"))
    )
    (net (code "188") (name "unconnected-(U4-NC_7-PadK4)") (class "Default")
      (node (ref "U4") (pin "K4") (pinfunction "NC_7_K4") (pintype "passive"))
    )
    (net (code "189") (name "unconnected-(U4-NC_8-PadK5)") (class "Default")
      (node (ref "U4") (pin "K5") (pinfunction "NC_8_K5") (pintype "passive"))
    )
  )
)
